# -_0617.net
KiCad netlist of a schematic drawn in EasyEDA Pro
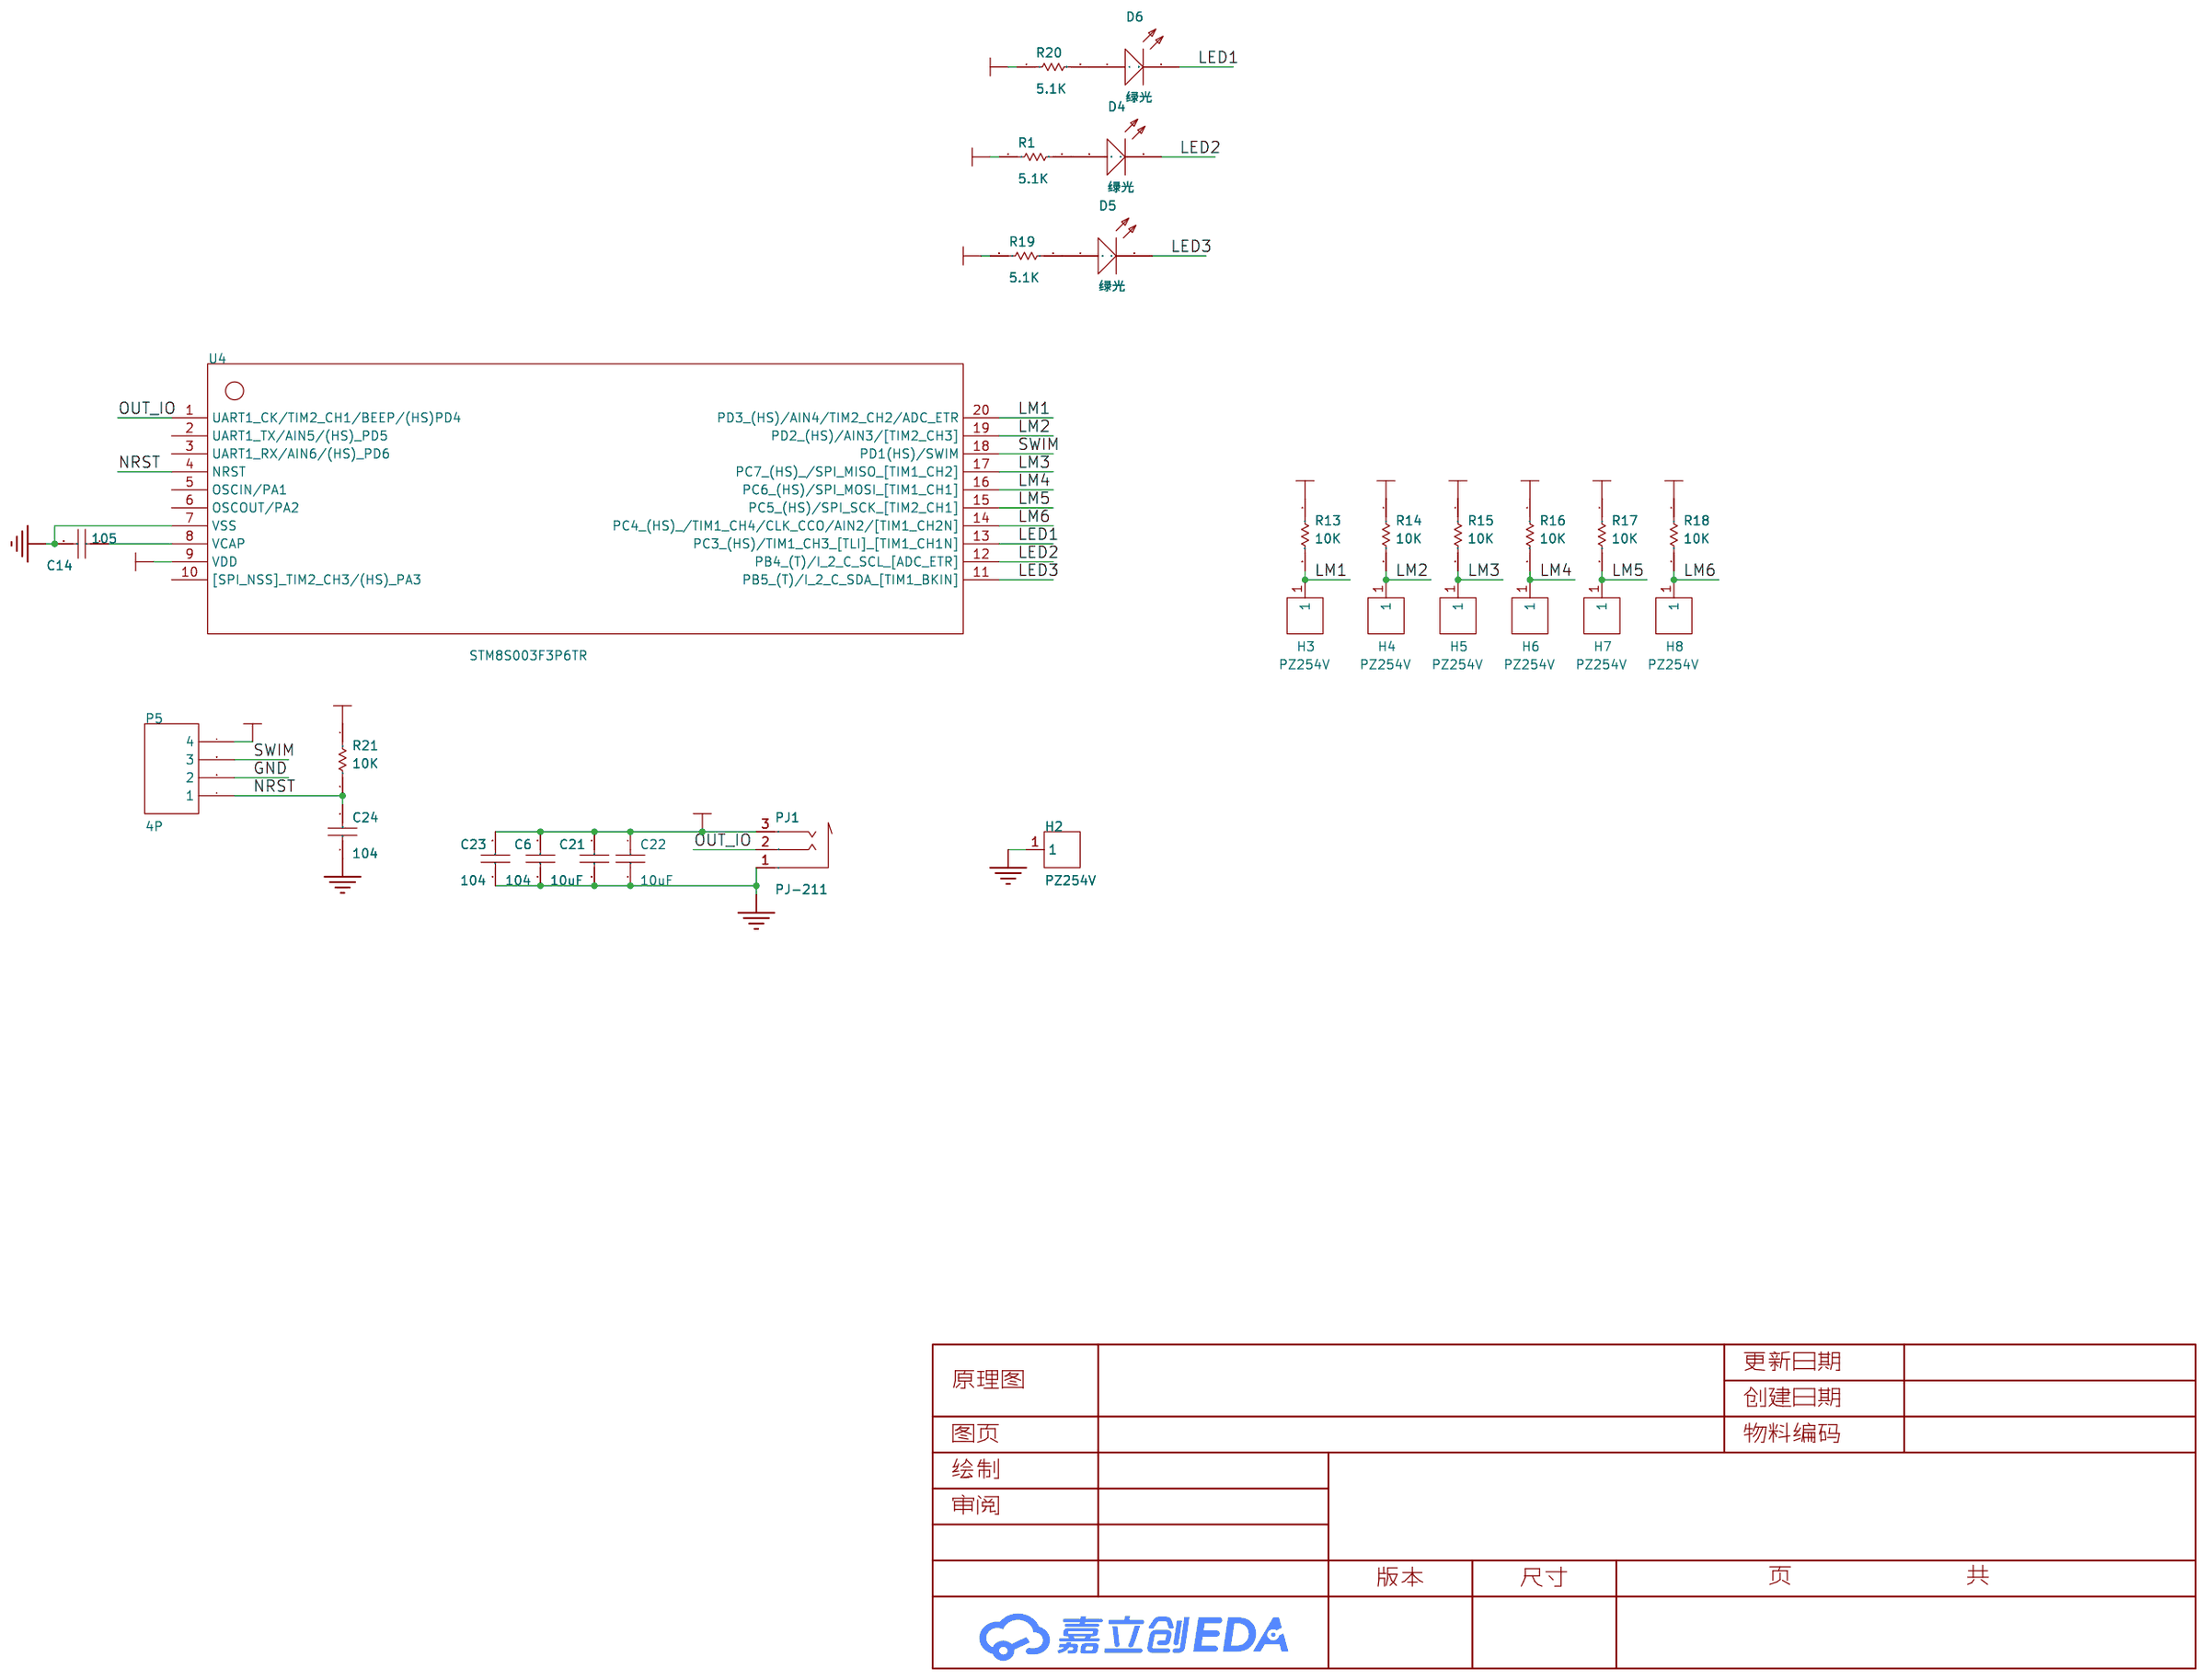
[diagram p0: schematic sheet]

(export (version "E")
  (design (tool "Eeschema 10.0.6"))
  (components
    (comp (ref "C6")
      (value "104")
      (footprint "easyedapro:0603C")
      (description "Capacitor (Semiconductor SIM Model)")
      (libsource (lib "easyedapro") (part "Cap Semi"))
    )
    (comp (ref "C14")
      (value "105")
      (footprint "easyedapro:0603C")
      (description "Capacitor (Semiconductor SIM Model)")
      (libsource (lib "easyedapro") (part "Cap Semi"))
    )
    (comp (ref "C21") (value "10uF") (libsource (lib "easyedapro") (part "CAP")))
    (comp (ref "C22") (value "10uF") (libsource (lib "easyedapro") (part "CAP")))
    (comp (ref "C23")
      (value "104")
      (footprint "easyedapro:0603C")
      (description "Capacitor (Semiconductor SIM Model)")
      (libsource (lib "easyedapro") (part "Cap Semi"))
    )
    (comp (ref "C24")
      (value "104")
      (footprint "easyedapro:0603C")
      (description "Capacitor (Semiconductor SIM Model)")
      (libsource (lib "easyedapro") (part "Cap Semi"))
    )
    (comp (ref "D4")
      (value "绿光")
      (footprint "easyedapro:0603LED")
      (libsource (lib "easyedapro") (part "LED"))
    )
    (comp (ref "D5")
      (value "绿光")
      (footprint "easyedapro:0603LED")
      (libsource (lib "easyedapro") (part "LED"))
    )
    (comp (ref "D6")
      (value "绿光")
      (footprint "easyedapro:0603LED")
      (libsource (lib "easyedapro") (part "LED"))
    )
    (comp (ref "H2")
      (value "PZ254V")
      (footprint "easyedapro:HDR-TH_1P-PZ254V-11-01P-YL")
      (description "排针2.54mm间距 直插 1x01位 黄色胶芯")
      (fields (field (name "Manufacturer") "XFCN(兴飞)"))
      (libsource (lib "easyedapro") (part "PZ254V-11-01P-YL"))
    )
    (comp (ref "H3")
      (value "PZ254V")
      (footprint "easyedapro:HDR-TH_1P-PZ254V-11-01P-YL")
      (description "排针2.54mm间距 直插 1x01位 黄色胶芯")
      (fields (field (name "Manufacturer") "XFCN(兴飞)"))
      (libsource (lib "easyedapro") (part "PZ254V-11-01P-YL"))
    )
    (comp (ref "H4")
      (value "PZ254V")
      (footprint "easyedapro:HDR-TH_1P-PZ254V-11-01P-YL")
      (description "排针2.54mm间距 直插 1x01位 黄色胶芯")
      (fields (field (name "Manufacturer") "XFCN(兴飞)"))
      (libsource (lib "easyedapro") (part "PZ254V-11-01P-YL"))
    )
    (comp (ref "H5")
      (value "PZ254V")
      (footprint "easyedapro:HDR-TH_1P-PZ254V-11-01P-YL")
      (description "排针2.54mm间距 直插 1x01位 黄色胶芯")
      (fields (field (name "Manufacturer") "XFCN(兴飞)"))
      (libsource (lib "easyedapro") (part "PZ254V-11-01P-YL"))
    )
    (comp (ref "H6")
      (value "PZ254V")
      (footprint "easyedapro:HDR-TH_1P-PZ254V-11-01P-YL")
      (description "排针2.54mm间距 直插 1x01位 黄色胶芯")
      (fields (field (name "Manufacturer") "XFCN(兴飞)"))
      (libsource (lib "easyedapro") (part "PZ254V-11-01P-YL"))
    )
    (comp (ref "H7")
      (value "PZ254V")
      (footprint "easyedapro:HDR-TH_1P-PZ254V-11-01P-YL")
      (description "排针2.54mm间距 直插 1x01位 黄色胶芯")
      (fields (field (name "Manufacturer") "XFCN(兴飞)"))
      (libsource (lib "easyedapro") (part "PZ254V-11-01P-YL"))
    )
    (comp (ref "H8")
      (value "PZ254V")
      (footprint "easyedapro:HDR-TH_1P-PZ254V-11-01P-YL")
      (description "排针2.54mm间距 直插 1x01位 黄色胶芯")
      (fields (field (name "Manufacturer") "XFCN(兴飞)"))
      (libsource (lib "easyedapro") (part "PZ254V-11-01P-YL"))
    )
    (comp (ref "P5") (value "4P") (libsource (lib "easyedapro") (part "4P")))
    (comp (ref "PJ1")
      (value "PJ-211")
      (footprint "easyedapro:AUDIO-TH_PJ-211")
      (description "连接器类型:2.5mm耳机座;额定电流:500mA;额定电压:30V;触头材质:铜;触头镀层:银;工作温度范围:-30°C~+70°C;")
      (fields (field (name "Manufacturer") "SHOU HAN(首韩)"))
      (libsource (lib "easyedapro") (part "PJ-211"))
    )
    (comp (ref "R1")
      (value "5.1K")
      (footprint "easyedapro:0603R")
      (description "Resistor")
      (libsource (lib "easyedapro") (part "RES"))
    )
    (comp (ref "R13")
      (value "10K")
      (footprint "easyedapro:0603R")
      (description "Resistor")
      (libsource (lib "easyedapro") (part "RES"))
    )
    (comp (ref "R14")
      (value "10K")
      (footprint "easyedapro:0603R")
      (description "Resistor")
      (libsource (lib "easyedapro") (part "RES"))
    )
    (comp (ref "R15")
      (value "10K")
      (footprint "easyedapro:0603R")
      (description "Resistor")
      (libsource (lib "easyedapro") (part "RES"))
    )
    (comp (ref "R16")
      (value "10K")
      (footprint "easyedapro:0603R")
      (description "Resistor")
      (libsource (lib "easyedapro") (part "RES"))
    )
    (comp (ref "R17")
      (value "10K")
      (footprint "easyedapro:0603R")
      (description "Resistor")
      (libsource (lib "easyedapro") (part "RES"))
    )
    (comp (ref "R18")
      (value "10K")
      (footprint "easyedapro:0603R")
      (description "Resistor")
      (libsource (lib "easyedapro") (part "RES"))
    )
    (comp (ref "R19")
      (value "5.1K")
      (footprint "easyedapro:0603R")
      (description "Resistor")
      (libsource (lib "easyedapro") (part "RES"))
    )
    (comp (ref "R20")
      (value "5.1K")
      (footprint "easyedapro:0603R")
      (description "Resistor")
      (libsource (lib "easyedapro") (part "RES"))
    )
    (comp (ref "R21")
      (value "10K")
      (footprint "easyedapro:0603R")
      (description "Resistor")
      (libsource (lib "easyedapro") (part "RES"))
    )
    (comp (ref "U4")
      (value "STM8S003F3P6TR")
      (footprint "easyedapro:TSSOP-20_L6.5-W4.4-P0.65-LS6.4-BL")
      (description "CPU内核:STM8;主频（MAX):16MHz;工作电压:2.95V~ 5.5V;")
      (fields (field (name "Manufacturer") "ST(意法半导体)"))
      (libsource (lib "easyedapro") (part "STM8S003F3P6TR"))
    )
  )
  (nets
    (net (code "1") (name "/LED1") (class "Default")
      (node (ref "D6") (pin "2") (pinfunction "2_2") (pintype "unspecified"))
      (node (ref "U4") (pin "13") (pinfunction "PC3_(HS)/TIM1_CH3_[TLI]_[TIM1_CH1N]_13") (pintype "input"))
    )
    (net (code "2") (name "/LED2") (class "Default")
      (node (ref "D4") (pin "2") (pinfunction "2_2") (pintype "unspecified"))
      (node (ref "U4") (pin "12") (pinfunction "PB4_(T)/I_2_C_SCL_[ADC_ETR]_12") (pintype "input"))
    )
    (net (code "3") (name "/LED3") (class "Default")
      (node (ref "D5") (pin "2") (pinfunction "2_2") (pintype "unspecified"))
      (node (ref "U4") (pin "11") (pinfunction "PB5_(T)/I_2_C_SDA_[TIM1_BKIN]_11") (pintype "input"))
    )
    (net (code "4") (name "/LM1") (class "Default")
      (node (ref "H3") (pin "1") (pinfunction "1_1") (pintype "unspecified"))
      (node (ref "R13") (pin "2") (pinfunction "2_2") (pintype "unspecified"))
      (node (ref "U4") (pin "20") (pinfunction "PD3_(HS)/AIN4/TIM2_CH2/ADC_ETR_20") (pintype "input"))
    )
    (net (code "5") (name "/LM2") (class "Default")
      (node (ref "H4") (pin "1") (pinfunction "1_1") (pintype "unspecified"))
      (node (ref "R14") (pin "2") (pinfunction "2_2") (pintype "unspecified"))
      (node (ref "U4") (pin "19") (pinfunction "PD2_(HS)/AIN3/[TIM2_CH3]_19") (pintype "input"))
    )
    (net (code "6") (name "/LM3") (class "Default")
      (node (ref "H5") (pin "1") (pinfunction "1_1") (pintype "unspecified"))
      (node (ref "R15") (pin "2") (pinfunction "2_2") (pintype "unspecified"))
      (node (ref "U4") (pin "17") (pinfunction "PC7_(HS)_/SPI_MISO_[TIM1_CH2]_17") (pintype "input"))
    )
    (net (code "7") (name "/LM4") (class "Default")
      (node (ref "H6") (pin "1") (pinfunction "1_1") (pintype "unspecified"))
      (node (ref "R16") (pin "2") (pinfunction "2_2") (pintype "unspecified"))
      (node (ref "U4") (pin "16") (pinfunction "PC6_(HS)/SPI_MOSI_[TIM1_CH1]_16") (pintype "input"))
    )
    (net (code "8") (name "/LM5") (class "Default")
      (node (ref "H7") (pin "1") (pinfunction "1_1") (pintype "unspecified"))
      (node (ref "R17") (pin "2") (pinfunction "2_2") (pintype "unspecified"))
      (node (ref "U4") (pin "15") (pinfunction "PC5_(HS)/SPI_SCK_[TIM2_CH1]_15") (pintype "input"))
    )
    (net (code "9") (name "/LM6") (class "Default")
      (node (ref "H8") (pin "1") (pinfunction "1_1") (pintype "unspecified"))
      (node (ref "R18") (pin "2") (pinfunction "2_2") (pintype "unspecified"))
      (node (ref "U4") (pin "14") (pinfunction "PC4_(HS)_/TIM1_CH4/CLK_CCO/AIN2/[TIM1_CH2N]_14") (pintype "input"))
    )
    (net (code "10") (name "/NRST") (class "Default")
      (node (ref "C24") (pin "2") (pinfunction "2_2") (pintype "unspecified"))
      (node (ref "P5") (pin "1") (pinfunction "1_1") (pintype "input"))
      (node (ref "R21") (pin "2") (pinfunction "2_2") (pintype "unspecified"))
      (node (ref "U4") (pin "4") (pinfunction "NRST_4") (pintype "input"))
    )
    (net (code "11") (name "/OUT_IO") (class "Default")
      (node (ref "PJ1") (pin "2") (pinfunction "2_2") (pintype "unspecified"))
      (node (ref "U4") (pin "1") (pinfunction "UART1_CK/TIM2_CH1/BEEP/(HS)PD4_1") (pintype "input"))
    )
    (net (code "12") (name "/SWIM") (class "Default")
      (node (ref "P5") (pin "3") (pinfunction "3_3") (pintype "input"))
      (node (ref "U4") (pin "18") (pinfunction "PD1(HS)/SWIM_18") (pintype "input"))
    )
    (net (code "13") (name "5V") (class "Default")
      (node (ref "C21") (pin "1") (pinfunction "1_1") (pintype "input"))
      (node (ref "C22") (pin "1") (pinfunction "1_1") (pintype "input"))
      (node (ref "C23") (pin "2") (pinfunction "2_2") (pintype "unspecified"))
      (node (ref "C6") (pin "2") (pinfunction "2_2") (pintype "unspecified"))
      (node (ref "P5") (pin "4") (pinfunction "4_4") (pintype "input"))
      (node (ref "PJ1") (pin "3") (pinfunction "3_3") (pintype "unspecified"))
      (node (ref "R1") (pin "1") (pinfunction "1_1") (pintype "unspecified"))
      (node (ref "R13") (pin "1") (pinfunction "1_1") (pintype "unspecified"))
      (node (ref "R14") (pin "1") (pinfunction "1_1") (pintype "unspecified"))
      (node (ref "R15") (pin "1") (pinfunction "1_1") (pintype "unspecified"))
      (node (ref "R16") (pin "1") (pinfunction "1_1") (pintype "unspecified"))
      (node (ref "R17") (pin "1") (pinfunction "1_1") (pintype "unspecified"))
      (node (ref "R18") (pin "1") (pinfunction "1_1") (pintype "unspecified"))
      (node (ref "R19") (pin "1") (pinfunction "1_1") (pintype "unspecified"))
      (node (ref "R20") (pin "1") (pinfunction "1_1") (pintype "unspecified"))
      (node (ref "R21") (pin "1") (pinfunction "1_1") (pintype "unspecified"))
      (node (ref "U4") (pin "9") (pinfunction "VDD_9") (pintype "input"))
    )
    (net (code "14") (name "GND") (class "Default")
      (node (ref "C14") (pin "2") (pinfunction "2_2") (pintype "unspecified"))
      (node (ref "C21") (pin "2") (pinfunction "2_2") (pintype "input"))
      (node (ref "C22") (pin "2") (pinfunction "2_2") (pintype "input"))
      (node (ref "C23") (pin "1") (pinfunction "1_1") (pintype "unspecified"))
      (node (ref "C24") (pin "1") (pinfunction "1_1") (pintype "unspecified"))
      (node (ref "C6") (pin "1") (pinfunction "1_1") (pintype "unspecified"))
      (node (ref "H2") (pin "1") (pinfunction "1_1") (pintype "unspecified"))
      (node (ref "P5") (pin "2") (pinfunction "2_2") (pintype "input"))
      (node (ref "PJ1") (pin "1") (pinfunction "1_1") (pintype "unspecified"))
      (node (ref "U4") (pin "7") (pinfunction "VSS_7") (pintype "input"))
    )
    (net (code "15") (name "Net-(D4-Pad1)") (class "Default")
      (node (ref "D4") (pin "1") (pinfunction "1_1") (pintype "unspecified"))
      (node (ref "R1") (pin "2") (pinfunction "2_2") (pintype "unspecified"))
    )
    (net (code "16") (name "Net-(D5-Pad1)") (class "Default")
      (node (ref "D5") (pin "1") (pinfunction "1_1") (pintype "unspecified"))
      (node (ref "R19") (pin "2") (pinfunction "2_2") (pintype "unspecified"))
    )
    (net (code "17") (name "Net-(D6-Pad1)") (class "Default")
      (node (ref "D6") (pin "1") (pinfunction "1_1") (pintype "unspecified"))
      (node (ref "R20") (pin "2") (pinfunction "2_2") (pintype "unspecified"))
    )
    (net (code "18") (name "Net-(U4-VCAP)") (class "Default")
      (node (ref "C14") (pin "1") (pinfunction "1_1") (pintype "unspecified"))
      (node (ref "U4") (pin "8") (pinfunction "VCAP_8") (pintype "input"))
    )
    (net (code "19") (name "unconnected-(U4-OSCIN{slash}PA1-Pad5)") (class "Default")
      (node (ref "U4") (pin "5") (pinfunction "OSCIN/PA1_5") (pintype "input"))
    )
    (net (code "20") (name "unconnected-(U4-OSCOUT{slash}PA2-Pad6)") (class "Default")
      (node (ref "U4") (pin "6") (pinfunction "OSCOUT/PA2_6") (pintype "input"))
    )
    (net (code "21") (name "unconnected-(U4-UART1_RX{slash}AIN6{slash}(HS)_PD6-Pad3)") (class "Default")
      (node (ref "U4") (pin "3") (pinfunction "UART1_RX/AIN6/(HS)_PD6_3") (pintype "input"))
    )
    (net (code "22") (name "unconnected-(U4-UART1_TX{slash}AIN5{slash}(HS)_PD5-Pad2)") (class "Default")
      (node (ref "U4") (pin "2") (pinfunction "UART1_TX/AIN5/(HS)_PD5_2") (pintype "input"))
    )
    (net (code "23") (name "unconnected-(U4-[SPI_NSS]_TIM2_CH3{slash}(HS)_PA3-Pad10)") (class "Default")
      (node (ref "U4") (pin "10") (pinfunction "[SPI_NSS]_TIM2_CH3/(HS)_PA3_10") (pintype "input"))
    )
  )
)
